# 6820-differential-interface.net
KiCad netlist of a schematic drawn in EAGLE
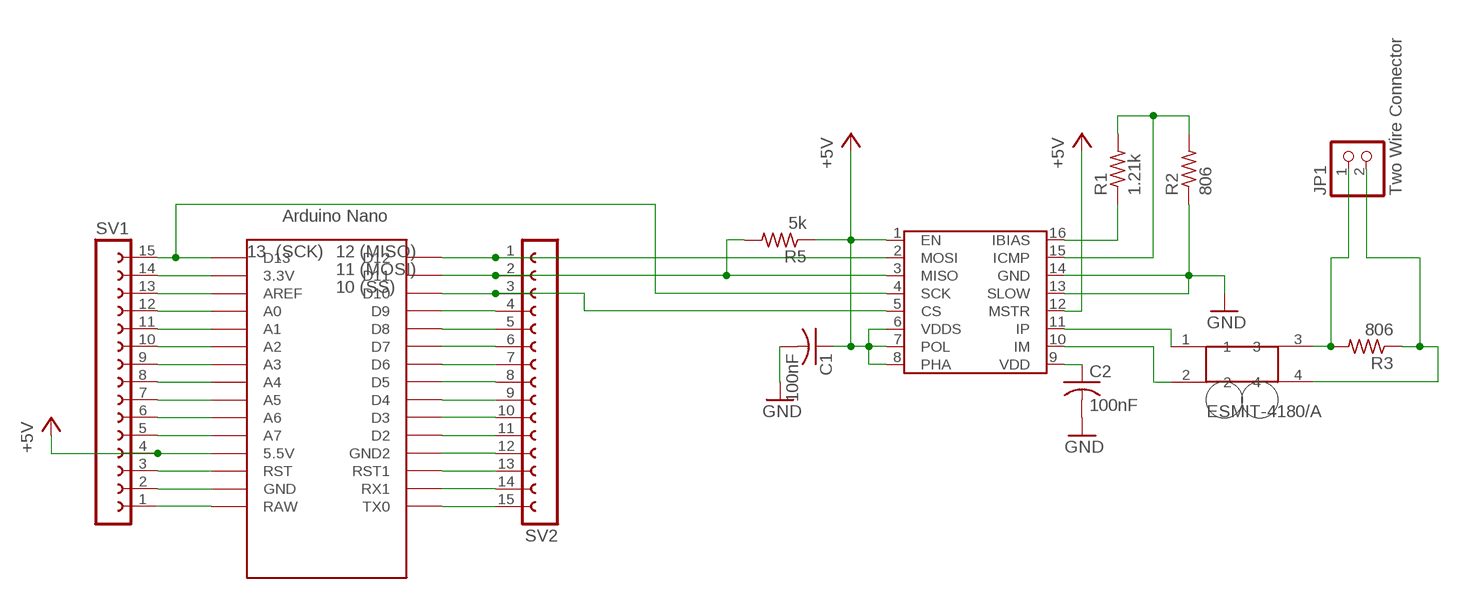
[diagram p0: schematic, sheet 1]

(export (version "E")
  (design (tool "Eeschema 10.0.6"))
  (components
    (comp (ref "C1")
      (value "100nF")
      (footprint "eagle-import:C0805")
      (libsource (lib "eagle-import") (part "C-USC0805"))
    )
    (comp (ref "C2")
      (value "100nF")
      (footprint "eagle-import:C0805")
      (libsource (lib "eagle-import") (part "C-USC0805"))
    )
    (comp (ref "JP1")
      (value "Two Wire Connector")
      (footprint "eagle-import:1X02")
      (libsource (lib "eagle-import") (part "PINHD-1X2"))
    )
    (comp (ref "R1")
      (value "1.21k")
      (footprint "eagle-import:R0805")
      (libsource (lib "eagle-import") (part "R-US_R0805"))
    )
    (comp (ref "R2")
      (value "806")
      (footprint "eagle-import:R0805")
      (libsource (lib "eagle-import") (part "R-US_R0805"))
    )
    (comp (ref "R3")
      (value "806")
      (footprint "eagle-import:R0805")
      (libsource (lib "eagle-import") (part "R-US_R0805"))
    )
    (comp (ref "R5")
      (value "5k")
      (footprint "eagle-import:R0805")
      (libsource (lib "eagle-import") (part "R-US_R0805"))
    )
    (comp (ref "SV1")
      (value "FE15-1")
      (footprint "eagle-import:FE15")
      (libsource (lib "eagle-import") (part "FE15-1"))
    )
    (comp (ref "SV2")
      (value "FE15-1")
      (footprint "eagle-import:FE15")
      (libsource (lib "eagle-import") (part "FE15-1"))
    )
    (comp (ref "U$1")
      (value "NANO")
      (footprint "eagle-import:NANO")
      (libsource (lib "eagle-import") (part "NANO"))
    )
    (comp (ref "U$2")
      (value "LTC6820")
      (footprint "eagle-import:MSOP-16")
      (libsource (lib "eagle-import") (part "LTC6820"))
    )
    (comp (ref "U$3")
      (value "ESMIT-4180/A")
      (footprint "eagle-import:ESMIT-4180_A")
      (libsource (lib "eagle-import") (part "ESMIT-4180/A"))
    )
  )
  (nets
    (net (code "1") (name "+5V") (class "Default")
      (node (ref "C1") (pin "1") (pinfunction "1_1") (pintype "passive"))
      (node (ref "R5") (pin "1") (pinfunction "1_1") (pintype "passive"))
      (node (ref "SV1") (pin "4") (pinfunction "4_4") (pintype "passive"))
      (node (ref "U$1") (pin "5V") (pinfunction "5.5V_5V") (pintype "bidirectional"))
      (node (ref "U$2") (pin "1") (pinfunction "EN_1") (pintype "bidirectional"))
      (node (ref "U$2") (pin "12") (pinfunction "MSTR_12") (pintype "bidirectional"))
      (node (ref "U$2") (pin "6") (pinfunction "VDDS_6") (pintype "bidirectional"))
      (node (ref "U$2") (pin "7") (pinfunction "POL_7") (pintype "bidirectional"))
      (node (ref "U$2") (pin "8") (pinfunction "PHA_8") (pintype "bidirectional"))
    )
    (net (code "2") (name "GND") (class "Default")
      (node (ref "C1") (pin "2") (pinfunction "2_2") (pintype "passive"))
      (node (ref "C2") (pin "2") (pinfunction "2_2") (pintype "passive"))
      (node (ref "R2") (pin "1") (pinfunction "1_1") (pintype "passive"))
      (node (ref "U$2") (pin "13") (pinfunction "SLOW_13") (pintype "bidirectional"))
      (node (ref "U$2") (pin "14") (pinfunction "GND_14") (pintype "bidirectional"))
    )
    (net (code "3") (name "Net-(JP1-Pad1)") (class "Default")
      (node (ref "JP1") (pin "1") (pinfunction "1_1") (pintype "passive"))
      (node (ref "R3") (pin "2") (pinfunction "2_2") (pintype "passive"))
      (node (ref "U$3") (pin "3") (pinfunction "3_3") (pintype "bidirectional"))
    )
    (net (code "4") (name "Net-(JP1-Pad2)") (class "Default")
      (node (ref "JP1") (pin "2") (pinfunction "2_2") (pintype "passive"))
      (node (ref "R3") (pin "1") (pinfunction "1_1") (pintype "passive"))
      (node (ref "U$3") (pin "4") (pinfunction "4_4") (pintype "bidirectional"))
    )
    (net (code "5") (name "Net-(SV1-Pad1)") (class "Default")
      (node (ref "SV1") (pin "1") (pinfunction "1_1") (pintype "passive"))
      (node (ref "U$1") (pin "RAW") (pinfunction "RAW_RAW") (pintype "bidirectional"))
    )
    (net (code "6") (name "Net-(SV1-Pad2)") (class "Default")
      (node (ref "SV1") (pin "2") (pinfunction "2_2") (pintype "passive"))
      (node (ref "U$1") (pin "GND") (pinfunction "GND_GND") (pintype "bidirectional"))
    )
    (net (code "7") (name "Net-(SV1-Pad3)") (class "Default")
      (node (ref "SV1") (pin "3") (pinfunction "3_3") (pintype "passive"))
      (node (ref "U$1") (pin "RST") (pinfunction "RST_RST") (pintype "bidirectional"))
    )
    (net (code "8") (name "Net-(SV1-Pad5)") (class "Default")
      (node (ref "SV1") (pin "5") (pinfunction "5_5") (pintype "passive"))
      (node (ref "U$1") (pin "A7") (pinfunction "A7_A7") (pintype "bidirectional"))
    )
    (net (code "9") (name "Net-(SV1-Pad6)") (class "Default")
      (node (ref "SV1") (pin "6") (pinfunction "6_6") (pintype "passive"))
      (node (ref "U$1") (pin "A6") (pinfunction "A6_A6") (pintype "bidirectional"))
    )
    (net (code "10") (name "Net-(SV1-Pad7)") (class "Default")
      (node (ref "SV1") (pin "7") (pinfunction "7_7") (pintype "passive"))
      (node (ref "U$1") (pin "A5") (pinfunction "A5_A5") (pintype "bidirectional"))
    )
    (net (code "11") (name "Net-(SV1-Pad8)") (class "Default")
      (node (ref "SV1") (pin "8") (pinfunction "8_8") (pintype "passive"))
      (node (ref "U$1") (pin "A4") (pinfunction "A4_A4") (pintype "bidirectional"))
    )
    (net (code "12") (name "Net-(SV1-Pad9)") (class "Default")
      (node (ref "SV1") (pin "9") (pinfunction "9_9") (pintype "passive"))
      (node (ref "U$1") (pin "A3") (pinfunction "A3_A3") (pintype "bidirectional"))
    )
    (net (code "13") (name "Net-(SV1-Pad10)") (class "Default")
      (node (ref "SV1") (pin "10") (pinfunction "10_10") (pintype "passive"))
      (node (ref "U$1") (pin "A2") (pinfunction "A2_A2") (pintype "bidirectional"))
    )
    (net (code "14") (name "Net-(SV1-Pad11)") (class "Default")
      (node (ref "SV1") (pin "11") (pinfunction "11_11") (pintype "passive"))
      (node (ref "U$1") (pin "A1") (pinfunction "A1_A1") (pintype "bidirectional"))
    )
    (net (code "15") (name "Net-(SV1-Pad12)") (class "Default")
      (node (ref "SV1") (pin "12") (pinfunction "12_12") (pintype "passive"))
      (node (ref "U$1") (pin "A0") (pinfunction "A0_A0") (pintype "bidirectional"))
    )
    (net (code "16") (name "Net-(SV1-Pad13)") (class "Default")
      (node (ref "SV1") (pin "13") (pinfunction "13_13") (pintype "passive"))
      (node (ref "U$1") (pin "AREF") (pinfunction "AREF_AREF") (pintype "bidirectional"))
    )
    (net (code "17") (name "Net-(SV1-Pad14)") (class "Default")
      (node (ref "SV1") (pin "14") (pinfunction "14_14") (pintype "passive"))
      (node (ref "U$1") (pin "3.3V") (pinfunction "3.3V_3.3V") (pintype "bidirectional"))
    )
    (net (code "18") (name "Net-(SV2-Pad4)") (class "Default")
      (node (ref "SV2") (pin "4") (pinfunction "4_4") (pintype "passive"))
      (node (ref "U$1") (pin "D9") (pinfunction "D9_D9") (pintype "bidirectional"))
    )
    (net (code "19") (name "Net-(SV2-Pad5)") (class "Default")
      (node (ref "SV2") (pin "5") (pinfunction "5_5") (pintype "passive"))
      (node (ref "U$1") (pin "D8") (pinfunction "D8_D8") (pintype "bidirectional"))
    )
    (net (code "20") (name "Net-(SV2-Pad6)") (class "Default")
      (node (ref "SV2") (pin "6") (pinfunction "6_6") (pintype "passive"))
      (node (ref "U$1") (pin "D7") (pinfunction "D7_D7") (pintype "bidirectional"))
    )
    (net (code "21") (name "Net-(SV2-Pad7)") (class "Default")
      (node (ref "SV2") (pin "7") (pinfunction "7_7") (pintype "passive"))
      (node (ref "U$1") (pin "D6") (pinfunction "D6_D6") (pintype "bidirectional"))
    )
    (net (code "22") (name "Net-(SV2-Pad8)") (class "Default")
      (node (ref "SV2") (pin "8") (pinfunction "8_8") (pintype "passive"))
      (node (ref "U$1") (pin "D5") (pinfunction "D5_D5") (pintype "bidirectional"))
    )
    (net (code "23") (name "Net-(SV2-Pad9)") (class "Default")
      (node (ref "SV2") (pin "9") (pinfunction "9_9") (pintype "passive"))
      (node (ref "U$1") (pin "D4") (pinfunction "D4_D4") (pintype "bidirectional"))
    )
    (net (code "24") (name "Net-(SV2-Pad10)") (class "Default")
      (node (ref "SV2") (pin "10") (pinfunction "10_10") (pintype "passive"))
      (node (ref "U$1") (pin "D3") (pinfunction "D3_D3") (pintype "bidirectional"))
    )
    (net (code "25") (name "Net-(SV2-Pad11)") (class "Default")
      (node (ref "SV2") (pin "11") (pinfunction "11_11") (pintype "passive"))
      (node (ref "U$1") (pin "D2") (pinfunction "D2_D2") (pintype "bidirectional"))
    )
    (net (code "26") (name "Net-(SV2-Pad13)") (class "Default")
      (node (ref "SV2") (pin "13") (pinfunction "13_13") (pintype "passive"))
      (node (ref "U$1") (pin "RST1") (pinfunction "RST1_RST1") (pintype "bidirectional"))
    )
    (net (code "27") (name "Net-(SV2-Pad14)") (class "Default")
      (node (ref "SV2") (pin "14") (pinfunction "14_14") (pintype "passive"))
      (node (ref "U$1") (pin "RX1") (pinfunction "RX1_RX1") (pintype "bidirectional"))
    )
    (net (code "28") (name "Net-(SV2-Pad15)") (class "Default")
      (node (ref "SV2") (pin "15") (pinfunction "15_15") (pintype "passive"))
      (node (ref "U$1") (pin "TX0") (pinfunction "TX0_TX0") (pintype "bidirectional"))
    )
    (net (code "29") (name "Net-(U$1-GND2)") (class "Default")
      (node (ref "SV2") (pin "12") (pinfunction "12_12") (pintype "passive"))
      (node (ref "U$1") (pin "GND1") (pinfunction "GND2_GND1") (pintype "bidirectional"))
    )
    (net (code "30") (name "Net-(U$2-CS)") (class "Default")
      (node (ref "SV2") (pin "3") (pinfunction "3_3") (pintype "passive"))
      (node (ref "U$1") (pin "D10") (pinfunction "D10_D10") (pintype "bidirectional"))
      (node (ref "U$2") (pin "5") (pinfunction "CS_5") (pintype "bidirectional"))
    )
    (net (code "31") (name "Net-(U$2-IBIAS)") (class "Default")
      (node (ref "R1") (pin "1") (pinfunction "1_1") (pintype "passive"))
      (node (ref "U$2") (pin "16") (pinfunction "IBIAS_16") (pintype "bidirectional"))
    )
    (net (code "32") (name "Net-(U$2-ICMP)") (class "Default")
      (node (ref "R1") (pin "2") (pinfunction "2_2") (pintype "passive"))
      (node (ref "R2") (pin "2") (pinfunction "2_2") (pintype "passive"))
      (node (ref "U$2") (pin "15") (pinfunction "ICMP_15") (pintype "bidirectional"))
    )
    (net (code "33") (name "Net-(U$2-IM)") (class "Default")
      (node (ref "U$2") (pin "10") (pinfunction "IM_10") (pintype "bidirectional"))
      (node (ref "U$3") (pin "2") (pinfunction "2_2") (pintype "bidirectional"))
    )
    (net (code "34") (name "Net-(U$2-IP)") (class "Default")
      (node (ref "U$2") (pin "11") (pinfunction "IP_11") (pintype "bidirectional"))
      (node (ref "U$3") (pin "1") (pinfunction "1_1") (pintype "bidirectional"))
    )
    (net (code "35") (name "Net-(U$2-MISO)") (class "Default")
      (node (ref "R5") (pin "2") (pinfunction "2_2") (pintype "passive"))
      (node (ref "SV2") (pin "2") (pinfunction "2_2") (pintype "passive"))
      (node (ref "U$1") (pin "D11") (pinfunction "D11_D11") (pintype "bidirectional"))
      (node (ref "U$2") (pin "3") (pinfunction "MISO_3") (pintype "bidirectional"))
    )
    (net (code "36") (name "Net-(U$2-MOSI)") (class "Default")
      (node (ref "SV2") (pin "1") (pinfunction "1_1") (pintype "passive"))
      (node (ref "U$1") (pin "D12") (pinfunction "D12_D12") (pintype "bidirectional"))
      (node (ref "U$2") (pin "2") (pinfunction "MOSI_2") (pintype "bidirectional"))
    )
    (net (code "37") (name "Net-(U$2-SCK)") (class "Default")
      (node (ref "SV1") (pin "15") (pinfunction "15_15") (pintype "passive"))
      (node (ref "U$1") (pin "D13") (pinfunction "D13_D13") (pintype "bidirectional"))
      (node (ref "U$2") (pin "4") (pinfunction "SCK_4") (pintype "bidirectional"))
    )
    (net (code "38") (name "Net-(U$2-VDD)") (class "Default")
      (node (ref "C2") (pin "1") (pinfunction "1_1") (pintype "passive"))
      (node (ref "U$2") (pin "9") (pinfunction "VDD_9") (pintype "bidirectional"))
    )
    (net (code "39") (name "unconnected-(U$1-PadICSP1)") (class "Default")
      (node (ref "U$1") (pin "ICSP1") (pinfunction "ICSP1_ICSP1") (pintype "bidirectional"))
    )
    (net (code "40") (name "unconnected-(U$1-PadICSP2)") (class "Default")
      (node (ref "U$1") (pin "ICSP2") (pinfunction "ICSP2_ICSP2") (pintype "bidirectional"))
    )
    (net (code "41") (name "unconnected-(U$1-PadICSP3)") (class "Default")
      (node (ref "U$1") (pin "ICSP3") (pinfunction "ICSP3_ICSP3") (pintype "bidirectional"))
    )
    (net (code "42") (name "unconnected-(U$1-PadICSP4)") (class "Default")
      (node (ref "U$1") (pin "ICSP4") (pinfunction "ICSP4_ICSP4") (pintype "bidirectional"))
    )
    (net (code "43") (name "unconnected-(U$1-PadICSP5)") (class "Default")
      (node (ref "U$1") (pin "ICSP5") (pinfunction "ICSP5_ICSP5") (pintype "bidirectional"))
    )
    (net (code "44") (name "unconnected-(U$1-PadICSP6)") (class "Default")
      (node (ref "U$1") (pin "ICSP6") (pinfunction "ICSP6_ICSP6") (pintype "bidirectional"))
    )
  )
)
